# Main_MCU.net
KiCad netlist of a schematic drawn in Altium Designer
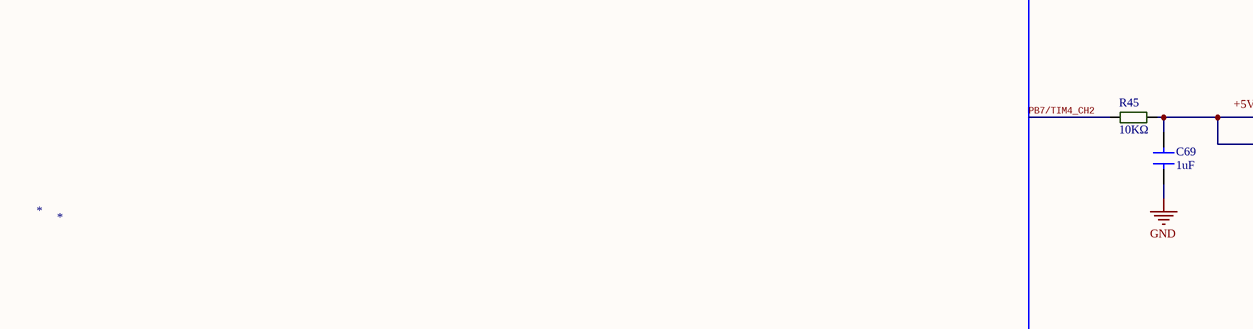
[diagram p0: Main MCU.SchDoc, left]
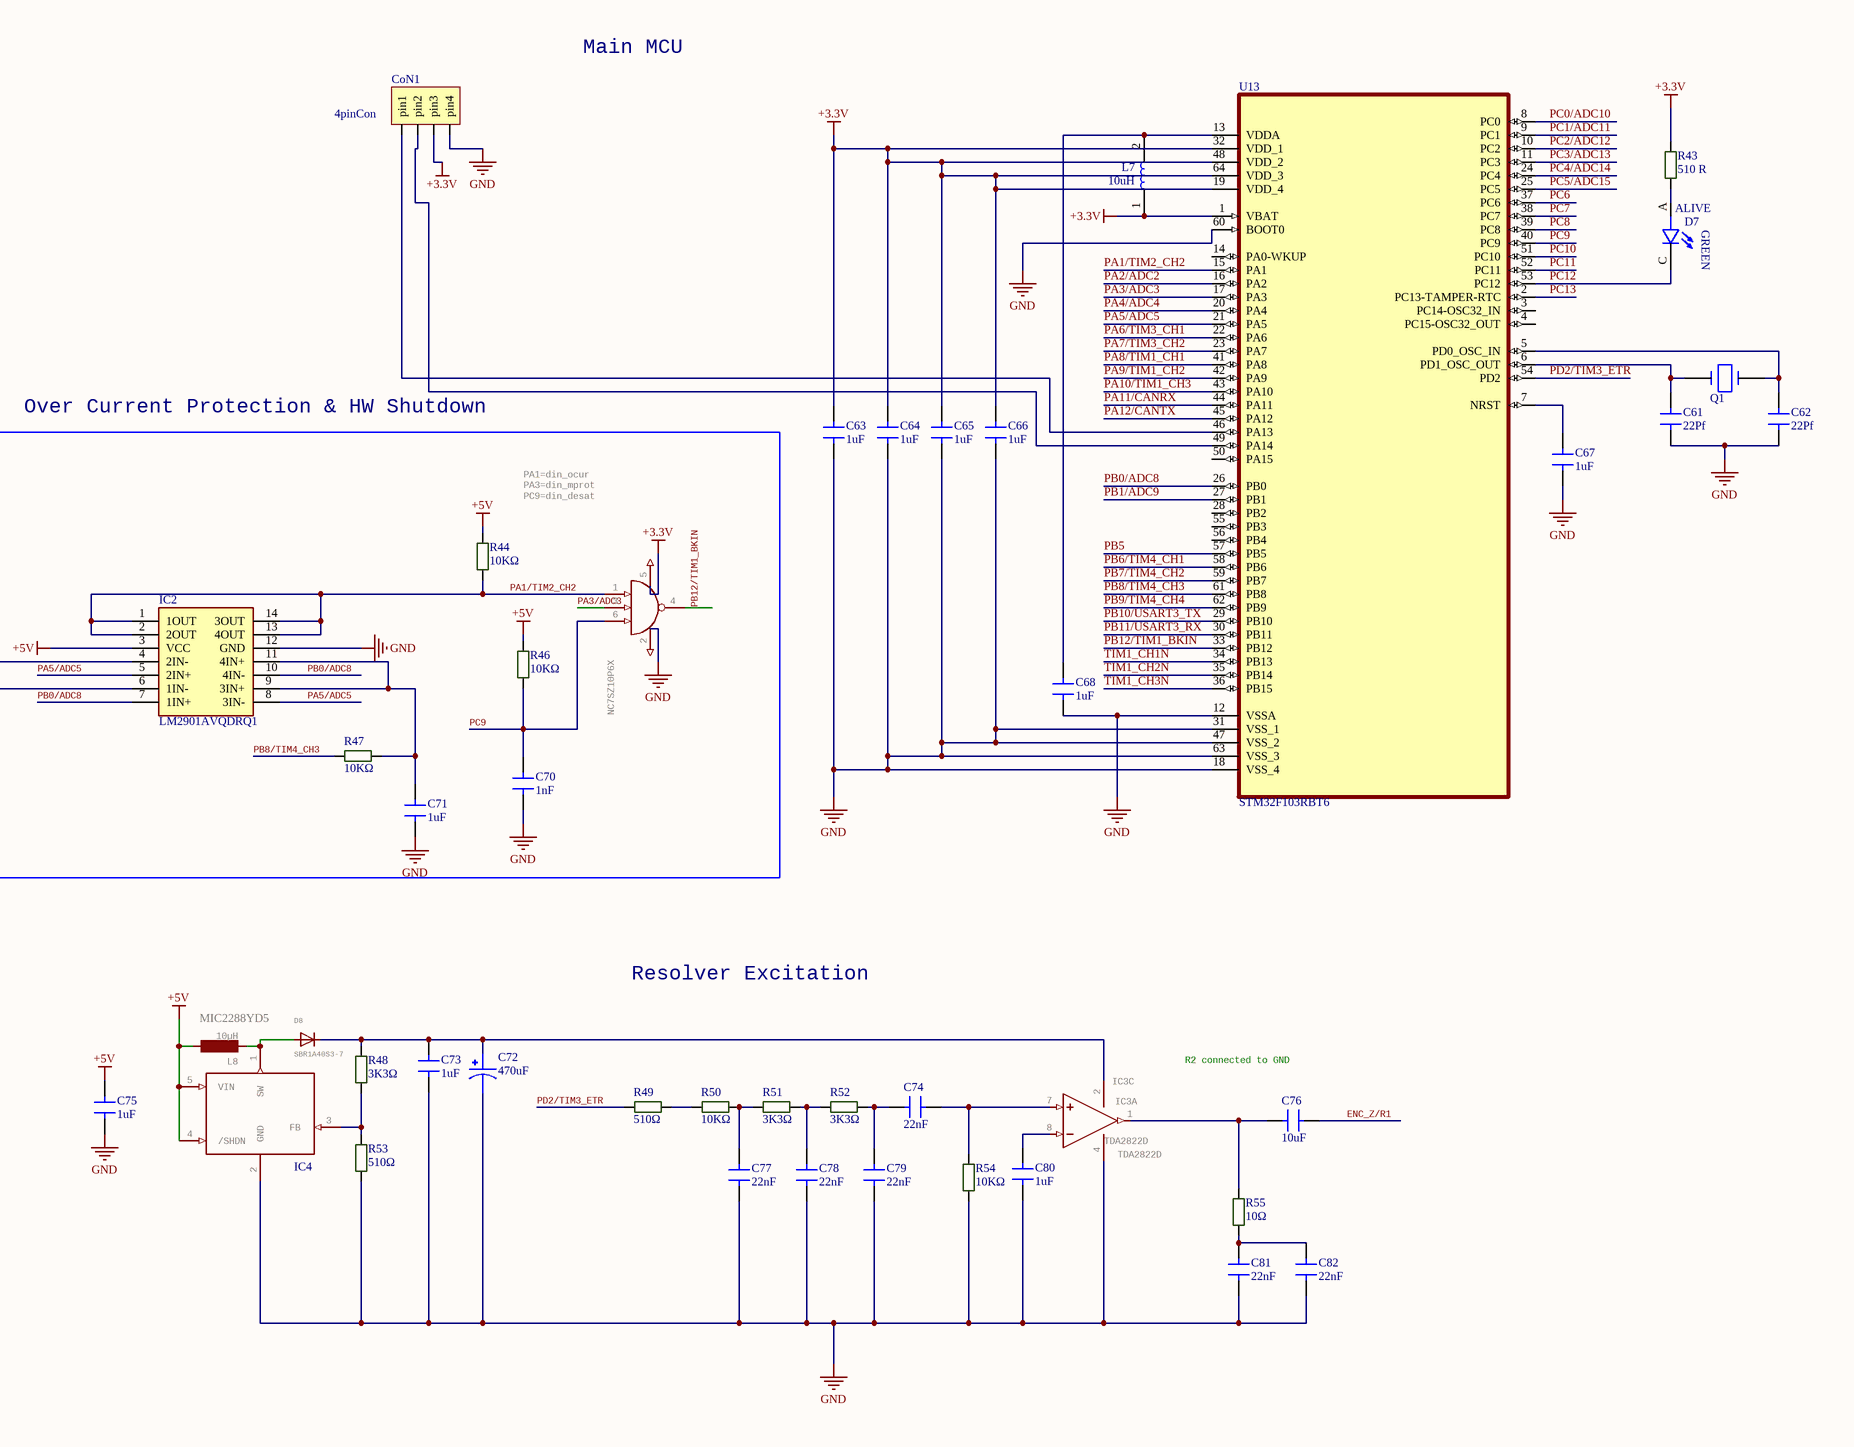
[diagram p1: Main MCU.SchDoc, right]

(export (version "E")
  (design (tool "Eeschema 10.0.6"))
  (components
    (comp (ref "C61")
      (value "22Pf")
      (footprint "C-0603W")
      (libsource (lib "Gate Driver Board") (part "C-0603"))
    )
    (comp (ref "C62")
      (value "22Pf")
      (footprint "C-0603W")
      (libsource (lib "Gate Driver Board") (part "C-0603"))
    )
    (comp (ref "C63")
      (value "1uF")
      (footprint "C-0603W")
      (libsource (lib "Gate Driver Board") (part "C-0603"))
    )
    (comp (ref "C64")
      (value "1uF")
      (footprint "C-0603W")
      (libsource (lib "Gate Driver Board") (part "C-0603"))
    )
    (comp (ref "C65")
      (value "1uF")
      (footprint "C-0603W")
      (libsource (lib "Gate Driver Board") (part "C-0603"))
    )
    (comp (ref "C66")
      (value "1uF")
      (footprint "C-0603W")
      (libsource (lib "Gate Driver Board") (part "C-0603"))
    )
    (comp (ref "C67")
      (value "1uF")
      (footprint "C-0603W")
      (libsource (lib "Gate Driver Board") (part "C-0603"))
    )
    (comp (ref "C68")
      (value "1uF")
      (footprint "C-0603W")
      (libsource (lib "Gate Driver Board") (part "C-0603"))
    )
    (comp (ref "C69")
      (value "1uF")
      (footprint "C-0603W")
      (libsource (lib "Gate Driver Board") (part "C-0603"))
    )
    (comp (ref "C70")
      (value "1nF")
      (footprint "C-0603W")
      (libsource (lib "Gate Driver Board") (part "C-0603"))
    )
    (comp (ref "C71")
      (value "1uF")
      (footprint "C-0603W")
      (libsource (lib "Gate Driver Board") (part "C-0603"))
    )
    (comp (ref "C72")
      (value "470uF")
      (footprint "CapSmdElc")
      (libsource (lib "PROJE") (part "100 uF Electr Cap"))
    )
    (comp (ref "C73")
      (value "1uF")
      (footprint "C-0603W")
      (libsource (lib "Gate Driver Board") (part "C-0603"))
    )
    (comp (ref "C74")
      (value "22nF")
      (footprint "C-0603W")
      (libsource (lib "Gate Driver Board") (part "C-0603"))
    )
    (comp (ref "C75")
      (value "1uF")
      (footprint "C-0603W")
      (libsource (lib "Gate Driver Board") (part "C-0603"))
    )
    (comp (ref "C76")
      (value "10uF")
      (footprint "C-0805")
      (libsource (lib "Gate Driver Board") (part "C-0805"))
    )
    (comp (ref "C77")
      (value "22nF")
      (footprint "C-0603W")
      (libsource (lib "Gate Driver Board") (part "C-0603"))
    )
    (comp (ref "C78")
      (value "22nF")
      (footprint "C-0603W")
      (libsource (lib "Gate Driver Board") (part "C-0603"))
    )
    (comp (ref "C79")
      (value "22nF")
      (footprint "C-0603W")
      (libsource (lib "Gate Driver Board") (part "C-0603"))
    )
    (comp (ref "C80")
      (value "1uF")
      (footprint "C-0603W")
      (libsource (lib "Gate Driver Board") (part "C-0603"))
    )
    (comp (ref "C81")
      (value "22nF")
      (footprint "C-0603W")
      (libsource (lib "Gate Driver Board") (part "C-0603"))
    )
    (comp (ref "C82")
      (value "22nF")
      (footprint "C-0603W")
      (libsource (lib "Gate Driver Board") (part "C-0603"))
    )
    (comp (ref "CoN1")
      (value "4pinCon")
      (footprint "4pinCon")
      (libsource (lib "Gate Driver Board") (part "4pinCon"))
    )
    (comp (ref "D7")
      (value "ALIVE")
      (footprint "LED_7012X1")
      (description "Green LED Indication - Discrete 1.7V 0805 (2012 Metric)")
      (fields (field (name "MP") "7012X1"))
      (libsource (lib "Gate Driver Board") (part "ALIVE"))
    )
    (comp (ref "D8")
      (value "*")
      (footprint "SOD-323F")
      (fields (field (name "ALTIUM_VALUE") "SBR1A40S3-7"))
      (libsource (lib "adafruit") (part "DIODESOD-323F"))
    )
    (comp (ref "IC1")
      (value "NC7SZ10P6X")
      (footprint "SC70-6")
      (description "3-input NAND gate")
      (libsource (lib "Gate Driver Board") (part "74*1G10X"))
    )
    (comp (ref "IC2")
      (value "LM2901AVQDRQ1")
      (footprint "SamacSys:SOIC127P600X175-14N")
      (description "Integrated Circuit")
      (fields (field (name "MOUSER PART NUMBER") "595-LM2901AVQDRQ1"))
      (libsource (lib "*") (part "LM2901AVQDRQ1"))
    )
    (comp (ref "IC3")
      (value "TDA2822D")
      (footprint "SO08")
      (description "OP AMP")
      (libsource (lib "Gate Driver Board") (part "TDA2822D"))
    )
    (comp (ref "IC4")
      (value "MIC2288YD5")
      (footprint "SOT23-5L")
      (libsource (lib "adafruit") (part "MIC2288YD5"))
    )
    (comp (ref "L7")
      (value "10uH")
      (footprint "INDC2012X87N")
      (description "FIXED IND 10UH 300MA 884 MOHM")
      (fields (field (name "MP") "MLZ2012M100HTD25"))
      (libsource (lib "Gate Driver Board") (part "MLZ2012M100HTD25"))
    )
    (comp (ref "L8")
      (value "*")
      (footprint "L2825P")
      (description "INDUCTOR, European symbol")
      (fields (field (name "ALTIUM_VALUE") "10µH"))
      (libsource (lib "rcl") (part "L-EUL2825P"))
    )
    (comp (ref "Q1")
      (value "Crystal 8MHz")
      (footprint "5032-2P")
      (description "32MHz Â±30ppm Crystal 18pF 40 Ohms HC-49/US")
      (fields (field (name "MF") "Abracon") (field (name "DIGI-KEY_PART_NUMBER") "535-9888-1-ND"))
      (libsource (lib "Gate Driver Board") (part "Crystal 8MHz"))
    )
    (comp (ref "R43")
      (value "510 R")
      (footprint "R-0603R")
      (libsource (lib "Gate Driver Board") (part "R-0603"))
    )
    (comp (ref "R44")
      (value "10KΩ")
      (footprint "R-0603R")
      (libsource (lib "Gate Driver Board") (part "R-0603"))
    )
    (comp (ref "R45")
      (value "10KΩ")
      (footprint "R-0603R")
      (libsource (lib "Gate Driver Board") (part "R-0603"))
    )
    (comp (ref "R46")
      (value "10KΩ")
      (footprint "R-0603R")
      (libsource (lib "Gate Driver Board") (part "R-0603"))
    )
    (comp (ref "R47")
      (value "10KΩ")
      (footprint "R-0603R")
      (libsource (lib "Gate Driver Board") (part "R-0603"))
    )
    (comp (ref "R48")
      (value "3K3Ω")
      (footprint "R-0603R")
      (libsource (lib "Gate Driver Board") (part "R-0603"))
    )
    (comp (ref "R49")
      (value "510Ω")
      (footprint "R-0603R")
      (libsource (lib "Gate Driver Board") (part "R-0603"))
    )
    (comp (ref "R50")
      (value "10KΩ")
      (footprint "R-0603R")
      (libsource (lib "Gate Driver Board") (part "R-0603"))
    )
    (comp (ref "R51")
      (value "3K3Ω")
      (footprint "R-0603R")
      (libsource (lib "Gate Driver Board") (part "R-0603"))
    )
    (comp (ref "R52")
      (value "3K3Ω")
      (footprint "R-0603R")
      (libsource (lib "Gate Driver Board") (part "R-0603"))
    )
    (comp (ref "R53")
      (value "510Ω")
      (footprint "R-0603R")
      (libsource (lib "Gate Driver Board") (part "R-0603"))
    )
    (comp (ref "R54")
      (value "10KΩ")
      (footprint "R-0603R")
      (libsource (lib "Gate Driver Board") (part "R-0603"))
    )
    (comp (ref "R55")
      (value "10Ω")
      (footprint "R-0603R")
      (libsource (lib "Gate Driver Board") (part "R-0603"))
    )
    (comp (ref "U13")
      (value "STM32F103RBT6")
      (footprint "QFP50P1200X1200X160-64N")
      (description "ARMÂ® CortexÂ®-M3 STM32F1 Microcontroller IC 32-Bit 72MHz 128KB _128K x 8_ FLASH")
      (fields (field (name "MF") "STMicroelectronics"))
      (libsource (lib "Gate Driver Board") (part "STM32F103RBT6"))
    )
  )
  (nets
    (net (code "1") (name "+3.3V") (class "Default")
      (node (ref "C63") (pin "2") (pinfunction "2_2") (pintype "passive"))
      (node (ref "C64") (pin "2") (pinfunction "2_2") (pintype "passive"))
      (node (ref "C65") (pin "2") (pinfunction "2_2") (pintype "passive"))
      (node (ref "C66") (pin "2") (pinfunction "2_2") (pintype "passive"))
      (node (ref "CoN1") (pin "3") (pinfunction "pin3_3") (pintype "passive"))
      (node (ref "IC1") (pin "5") (pinfunction "I0_5") (pintype "input"))
      (node (ref "L7") (pin "1") (pinfunction "1_1") (pintype "passive"))
      (node (ref "R43") (pin "2") (pinfunction "2_2") (pintype "passive"))
      (node (ref "U13") (pin "1") (pinfunction "VBAT_1") (pintype "input"))
      (node (ref "U13") (pin "19") (pinfunction "VDD_4_19") (pintype "power_in"))
      (node (ref "U13") (pin "32") (pinfunction "VDD_1_32") (pintype "power_in"))
      (node (ref "U13") (pin "48") (pinfunction "VDD_2_48") (pintype "power_in"))
      (node (ref "U13") (pin "64") (pinfunction "VDD_3_64") (pintype "power_in"))
    )
    (net (code "2") (name "+5V") (class "Default")
      (node (ref "C75") (pin "2") (pinfunction "2_2") (pintype "passive"))
      (node (ref "IC2") (pin "3") (pinfunction "VCC_3") (pintype "passive"))
      (node (ref "IC4") (pin "4") (pinfunction "/SHDN_4") (pintype "input"))
      (node (ref "IC4") (pin "5") (pinfunction "VIN_5") (pintype "input"))
      (node (ref "L8") (pin "1") (pinfunction "1_1") (pintype "passive"))
      (node (ref "R44") (pin "2") (pinfunction "2_2") (pintype "passive"))
      (node (ref "R46") (pin "2") (pinfunction "2_2") (pintype "passive"))
    )
    (net (code "3") (name "/ENC_Z{slash}R1") (class "Default")
      (node (ref "C76") (pin "2") (pinfunction "2_2") (pintype "passive"))
    )
    (net (code "4") (name "/PA1{slash}TIM2_CH2") (class "Default")
      (node (ref "IC1") (pin "1") (pinfunction "I0_1") (pintype "input"))
      (node (ref "IC2") (pin "1") (pinfunction "1OUT_1") (pintype "passive"))
      (node (ref "IC2") (pin "13") (pinfunction "4OUT_13") (pintype "passive"))
      (node (ref "IC2") (pin "14") (pinfunction "3OUT_14") (pintype "passive"))
      (node (ref "IC2") (pin "2") (pinfunction "2OUT_2") (pintype "passive"))
      (node (ref "R44") (pin "1") (pinfunction "1_1") (pintype "passive"))
      (node (ref "U13") (pin "15") (pinfunction "PA1_15") (pintype "bidirectional"))
    )
    (net (code "5") (name "/PA2{slash}ADC2") (class "Default")
      (node (ref "U13") (pin "16") (pinfunction "PA2_16") (pintype "bidirectional"))
    )
    (net (code "6") (name "/PA3{slash}ADC3") (class "Default")
      (node (ref "IC1") (pin "3") (pinfunction "I1_3") (pintype "input"))
      (node (ref "U13") (pin "17") (pinfunction "PA3_17") (pintype "bidirectional"))
    )
    (net (code "7") (name "/PA4{slash}ADC4") (class "Default")
      (node (ref "U13") (pin "20") (pinfunction "PA4_20") (pintype "bidirectional"))
    )
    (net (code "8") (name "/PA5{slash}ADC5") (class "Default")
      (node (ref "IC2") (pin "5") (pinfunction "2IN+_5") (pintype "passive"))
      (node (ref "IC2") (pin "8") (pinfunction "3IN-_8") (pintype "passive"))
      (node (ref "U13") (pin "21") (pinfunction "PA5_21") (pintype "bidirectional"))
    )
    (net (code "9") (name "/PA6{slash}TIM3_CH1") (class "Default")
      (node (ref "U13") (pin "22") (pinfunction "PA6_22") (pintype "bidirectional"))
    )
    (net (code "10") (name "/PA7{slash}TIM3_CH2") (class "Default")
      (node (ref "U13") (pin "23") (pinfunction "PA7_23") (pintype "bidirectional"))
    )
    (net (code "11") (name "/PA8{slash}TIM1_CH1") (class "Default")
      (node (ref "U13") (pin "41") (pinfunction "PA8_41") (pintype "bidirectional"))
    )
    (net (code "12") (name "/PA9{slash}TIM1_CH2") (class "Default")
      (node (ref "U13") (pin "42") (pinfunction "PA9_42") (pintype "bidirectional"))
    )
    (net (code "13") (name "/PA10{slash}TIM1_CH3") (class "Default")
      (node (ref "U13") (pin "43") (pinfunction "PA10_43") (pintype "bidirectional"))
    )
    (net (code "14") (name "/PA11{slash}CANRX") (class "Default")
      (node (ref "U13") (pin "44") (pinfunction "PA11_44") (pintype "bidirectional"))
    )
    (net (code "15") (name "/PA12{slash}CANTX") (class "Default")
      (node (ref "U13") (pin "45") (pinfunction "PA12_45") (pintype "bidirectional"))
    )
    (net (code "16") (name "/PB0{slash}ADC8") (class "Default")
      (node (ref "IC2") (pin "10") (pinfunction "4IN-_10") (pintype "passive"))
      (node (ref "IC2") (pin "7") (pinfunction "1IN+_7") (pintype "passive"))
      (node (ref "U13") (pin "26") (pinfunction "PB0_26") (pintype "bidirectional"))
    )
    (net (code "17") (name "/PB1{slash}ADC9") (class "Default")
      (node (ref "U13") (pin "27") (pinfunction "PB1_27") (pintype "bidirectional"))
    )
    (net (code "18") (name "/PB5") (class "Default")
      (node (ref "U13") (pin "57") (pinfunction "PB5_57") (pintype "bidirectional"))
    )
    (net (code "19") (name "/PB6{slash}TIM4_CH1") (class "Default")
      (node (ref "U13") (pin "58") (pinfunction "PB6_58") (pintype "bidirectional"))
    )
    (net (code "20") (name "/PB7{slash}TIM4_CH2") (class "Default")
      (node (ref "R45") (pin "1") (pinfunction "1_1") (pintype "passive"))
      (node (ref "U13") (pin "59") (pinfunction "PB7_59") (pintype "bidirectional"))
    )
    (net (code "21") (name "/PB8{slash}TIM4_CH3") (class "Default")
      (node (ref "R47") (pin "1") (pinfunction "1_1") (pintype "passive"))
      (node (ref "U13") (pin "61") (pinfunction "PB8_61") (pintype "bidirectional"))
    )
    (net (code "22") (name "/PB9{slash}TIM4_CH4") (class "Default")
      (node (ref "U13") (pin "62") (pinfunction "PB9_62") (pintype "bidirectional"))
    )
    (net (code "23") (name "/PB10{slash}USART3_TX") (class "Default")
      (node (ref "U13") (pin "29") (pinfunction "PB10_29") (pintype "bidirectional"))
    )
    (net (code "24") (name "/PB11{slash}USART3_RX") (class "Default")
      (node (ref "U13") (pin "30") (pinfunction "PB11_30") (pintype "bidirectional"))
    )
    (net (code "25") (name "/PB12{slash}TIM1_BKIN") (class "Default")
      (node (ref "IC1") (pin "4") (pinfunction "O_4") (pintype "open_collector"))
      (node (ref "U13") (pin "33") (pinfunction "PB12_33") (pintype "bidirectional"))
    )
    (net (code "26") (name "/PC0{slash}ADC10") (class "Default")
      (node (ref "U13") (pin "8") (pinfunction "PC0_8") (pintype "bidirectional"))
    )
    (net (code "27") (name "/PC1{slash}ADC11") (class "Default")
      (node (ref "U13") (pin "9") (pinfunction "PC1_9") (pintype "bidirectional"))
    )
    (net (code "28") (name "/PC2{slash}ADC12") (class "Default")
      (node (ref "U13") (pin "10") (pinfunction "PC2_10") (pintype "bidirectional"))
    )
    (net (code "29") (name "/PC3{slash}ADC13") (class "Default")
      (node (ref "U13") (pin "11") (pinfunction "PC3_11") (pintype "bidirectional"))
    )
    (net (code "30") (name "/PC4{slash}ADC14") (class "Default")
      (node (ref "U13") (pin "24") (pinfunction "PC4_24") (pintype "bidirectional"))
    )
    (net (code "31") (name "/PC5{slash}ADC15") (class "Default")
      (node (ref "U13") (pin "25") (pinfunction "PC5_25") (pintype "bidirectional"))
    )
    (net (code "32") (name "/PC6") (class "Default")
      (node (ref "U13") (pin "37") (pinfunction "PC6_37") (pintype "bidirectional"))
    )
    (net (code "33") (name "/PC7") (class "Default")
      (node (ref "U13") (pin "38") (pinfunction "PC7_38") (pintype "bidirectional"))
    )
    (net (code "34") (name "/PC8") (class "Default")
      (node (ref "U13") (pin "39") (pinfunction "PC8_39") (pintype "bidirectional"))
    )
    (net (code "35") (name "/PC9") (class "Default")
      (node (ref "C70") (pin "2") (pinfunction "2_2") (pintype "passive"))
      (node (ref "IC1") (pin "6") (pinfunction "I2_6") (pintype "input"))
      (node (ref "R46") (pin "1") (pinfunction "1_1") (pintype "passive"))
      (node (ref "U13") (pin "40") (pinfunction "PC9_40") (pintype "bidirectional"))
    )
    (net (code "36") (name "/PC10") (class "Default")
      (node (ref "U13") (pin "51") (pinfunction "PC10_51") (pintype "bidirectional"))
    )
    (net (code "37") (name "/PC11") (class "Default")
      (node (ref "U13") (pin "52") (pinfunction "PC11_52") (pintype "bidirectional"))
    )
    (net (code "38") (name "/PC12") (class "Default")
      (node (ref "D7") (pin "C") (pinfunction "C_C") (pintype "passive"))
      (node (ref "U13") (pin "53") (pinfunction "PC12_53") (pintype "bidirectional"))
    )
    (net (code "39") (name "/PC13") (class "Default")
      (node (ref "U13") (pin "2") (pinfunction "PC13-TAMPER-RTC_2") (pintype "bidirectional"))
    )
    (net (code "40") (name "/PD2{slash}TIM3_ETR") (class "Default")
      (node (ref "R49") (pin "2") (pinfunction "2_2") (pintype "passive"))
      (node (ref "U13") (pin "54") (pinfunction "PD2_54") (pintype "bidirectional"))
    )
    (net (code "41") (name "/TIM1_CH1N") (class "Default")
      (node (ref "U13") (pin "34") (pinfunction "PB13_34") (pintype "bidirectional"))
    )
    (net (code "42") (name "/TIM1_CH2N") (class "Default")
      (node (ref "U13") (pin "35") (pinfunction "PB14_35") (pintype "bidirectional"))
    )
    (net (code "43") (name "/TIM1_CH3N") (class "Default")
      (node (ref "U13") (pin "36") (pinfunction "PB15_36") (pintype "bidirectional"))
    )
    (net (code "44") (name "GND") (class "Default")
      (node (ref "C61") (pin "1") (pinfunction "1_1") (pintype "passive"))
      (node (ref "C62") (pin "1") (pinfunction "1_1") (pintype "passive"))
      (node (ref "C63") (pin "1") (pinfunction "1_1") (pintype "passive"))
      (node (ref "C64") (pin "1") (pinfunction "1_1") (pintype "passive"))
      (node (ref "C65") (pin "1") (pinfunction "1_1") (pintype "passive"))
      (node (ref "C66") (pin "1") (pinfunction "1_1") (pintype "passive"))
      (node (ref "C67") (pin "1") (pinfunction "1_1") (pintype "passive"))
      (node (ref "C68") (pin "1") (pinfunction "1_1") (pintype "passive"))
      (node (ref "C69") (pin "1") (pinfunction "1_1") (pintype "passive"))
      (node (ref "C70") (pin "1") (pinfunction "1_1") (pintype "passive"))
      (node (ref "C71") (pin "1") (pinfunction "1_1") (pintype "passive"))
      (node (ref "C72") (pin "2") (pinfunction "2_2") (pintype "passive"))
      (node (ref "C73") (pin "1") (pinfunction "1_1") (pintype "passive"))
      (node (ref "C75") (pin "1") (pinfunction "1_1") (pintype "passive"))
      (node (ref "C77") (pin "1") (pinfunction "1_1") (pintype "passive"))
      (node (ref "C78") (pin "1") (pinfunction "1_1") (pintype "passive"))
      (node (ref "C79") (pin "1") (pinfunction "1_1") (pintype "passive"))
      (node (ref "C80") (pin "1") (pinfunction "1_1") (pintype "passive"))
      (node (ref "C81") (pin "1") (pinfunction "1_1") (pintype "passive"))
      (node (ref "C82") (pin "1") (pinfunction "1_1") (pintype "passive"))
      (node (ref "CoN1") (pin "4") (pinfunction "pin4_4") (pintype "passive"))
      (node (ref "IC1") (pin "2") (pinfunction "I0_2") (pintype "input"))
      (node (ref "IC2") (pin "12") (pinfunction "GND_12") (pintype "passive"))
      (node (ref "IC3") (pin "4") (pinfunction "V-_4") (pintype "power_in"))
      (node (ref "IC4") (pin "2") (pinfunction "GND_2") (pintype "power_in"))
      (node (ref "R53") (pin "2") (pinfunction "2_2") (pintype "passive"))
      (node (ref "R54") (pin "1") (pinfunction "1_1") (pintype "passive"))
      (node (ref "U13") (pin "12") (pinfunction "VSSA_12") (pintype "passive"))
      (node (ref "U13") (pin "18") (pinfunction "VSS_4_18") (pintype "passive"))
      (node (ref "U13") (pin "31") (pinfunction "VSS_1_31") (pintype "passive"))
      (node (ref "U13") (pin "47") (pinfunction "VSS_2_47") (pintype "passive"))
      (node (ref "U13") (pin "60") (pinfunction "BOOT0_60") (pintype "input"))
      (node (ref "U13") (pin "63") (pinfunction "VSS_3_63") (pintype "passive"))
    )
    (net (code "45") (name "Net-(C74-Pad2)") (class "Default")
      (node (ref "C74") (pin "2") (pinfunction "2_2") (pintype "passive"))
      (node (ref "C79") (pin "2") (pinfunction "2_2") (pintype "passive"))
      (node (ref "R52") (pin "2") (pinfunction "2_2") (pintype "passive"))
    )
    (net (code "46") (name "Net-(C77-Pad2)") (class "Default")
      (node (ref "C77") (pin "2") (pinfunction "2_2") (pintype "passive"))
      (node (ref "R50") (pin "1") (pinfunction "1_1") (pintype "passive"))
      (node (ref "R51") (pin "1") (pinfunction "1_1") (pintype "passive"))
    )
    (net (code "47") (name "Net-(C78-Pad2)") (class "Default")
      (node (ref "C78") (pin "2") (pinfunction "2_2") (pintype "passive"))
      (node (ref "R51") (pin "2") (pinfunction "2_2") (pintype "passive"))
      (node (ref "R52") (pin "1") (pinfunction "1_1") (pintype "passive"))
    )
    (net (code "48") (name "Net-(C81-Pad2)") (class "Default")
      (node (ref "C81") (pin "2") (pinfunction "2_2") (pintype "passive"))
      (node (ref "C82") (pin "2") (pinfunction "2_2") (pintype "passive"))
      (node (ref "R55") (pin "2") (pinfunction "2_2") (pintype "passive"))
    )
    (net (code "49") (name "Net-(CoN1-pin1)") (class "Default")
      (node (ref "CoN1") (pin "1") (pinfunction "pin1_1") (pintype "passive"))
      (node (ref "U13") (pin "46") (pinfunction "PA13_46") (pintype "bidirectional"))
    )
    (net (code "50") (name "Net-(CoN1-pin2)") (class "Default")
      (node (ref "CoN1") (pin "2") (pinfunction "pin2_2") (pintype "passive"))
      (node (ref "U13") (pin "49") (pinfunction "PA14_49") (pintype "bidirectional"))
    )
    (net (code "51") (name "Net-(D7-PadA)") (class "Default")
      (node (ref "D7") (pin "A") (pinfunction "A_A") (pintype "passive"))
      (node (ref "R43") (pin "1") (pinfunction "1_1") (pintype "passive"))
    )
    (net (code "52") (name "Net-(IC2-1IN-)") (class "Default")
      (node (ref "C69") (pin "2") (pinfunction "2_2") (pintype "passive"))
      (node (ref "IC2") (pin "4") (pinfunction "2IN-_4") (pintype "passive"))
      (node (ref "IC2") (pin "6") (pinfunction "1IN-_6") (pintype "passive"))
      (node (ref "R45") (pin "2") (pinfunction "2_2") (pintype "passive"))
    )
    (net (code "53") (name "Net-(IC2-3IN+)") (class "Default")
      (node (ref "C71") (pin "2") (pinfunction "2_2") (pintype "passive"))
      (node (ref "IC2") (pin "11") (pinfunction "4IN+_11") (pintype "passive"))
      (node (ref "IC2") (pin "9") (pinfunction "3IN+_9") (pintype "passive"))
      (node (ref "R47") (pin "2") (pinfunction "2_2") (pintype "passive"))
    )
    (net (code "54") (name "Net-(IC3A-+IN)") (class "Default")
      (node (ref "C74") (pin "1") (pinfunction "1_1") (pintype "passive"))
      (node (ref "IC3") (pin "7") (pinfunction "+IN_7") (pintype "input"))
      (node (ref "R54") (pin "2") (pinfunction "2_2") (pintype "passive"))
    )
    (net (code "55") (name "Net-(IC3A--IN)") (class "Default")
      (node (ref "C80") (pin "2") (pinfunction "2_2") (pintype "passive"))
      (node (ref "IC3") (pin "8") (pinfunction "-IN_8") (pintype "input"))
    )
    (net (code "56") (name "Net-(IC3A-OUT)") (class "Default")
      (node (ref "C76") (pin "1") (pinfunction "1_1") (pintype "passive"))
      (node (ref "IC3") (pin "1") (pinfunction "OUT_1") (pintype "output"))
      (node (ref "R55") (pin "1") (pinfunction "1_1") (pintype "passive"))
    )
    (net (code "57") (name "Net-(IC3C-V+)") (class "Default")
      (node (ref "C72") (pin "1") (pinfunction "1_1") (pintype "passive"))
      (node (ref "C73") (pin "2") (pinfunction "2_2") (pintype "passive"))
      (node (ref "D8") (pin "C") (pinfunction "C_C") (pintype "passive"))
      (node (ref "IC3") (pin "2") (pinfunction "V+_2") (pintype "power_in"))
      (node (ref "R48") (pin "2") (pinfunction "2_2") (pintype "passive"))
    )
    (net (code "58") (name "Net-(IC4-FB)") (class "Default")
      (node (ref "IC4") (pin "3") (pinfunction "FB_3") (pintype "input"))
      (node (ref "R48") (pin "1") (pinfunction "1_1") (pintype "passive"))
      (node (ref "R53") (pin "1") (pinfunction "1_1") (pintype "passive"))
    )
    (net (code "59") (name "Net-(IC4-SW)") (class "Default")
      (node (ref "D8") (pin "A") (pinfunction "A_A") (pintype "passive"))
      (node (ref "IC4") (pin "1") (pinfunction "SW_1") (pintype "output"))
      (node (ref "L8") (pin "2") (pinfunction "2_2") (pintype "passive"))
    )
    (net (code "60") (name "Net-(R49-Pad1)") (class "Default")
      (node (ref "R49") (pin "1") (pinfunction "1_1") (pintype "passive"))
      (node (ref "R50") (pin "2") (pinfunction "2_2") (pintype "passive"))
    )
    (net (code "61") (name "Net-(U13-NRST)") (class "Default")
      (node (ref "C67") (pin "2") (pinfunction "2_2") (pintype "passive"))
      (node (ref "U13") (pin "7") (pinfunction "NRST_7") (pintype "bidirectional"))
    )
    (net (code "62") (name "Net-(U13-PD0_OSC_IN)") (class "Default")
      (node (ref "C62") (pin "2") (pinfunction "2_2") (pintype "passive"))
      (node (ref "Q1") (pin "2") (pinfunction "2_2") (pintype "passive"))
      (node (ref "U13") (pin "5") (pinfunction "PD0_OSC_IN_5") (pintype "bidirectional"))
    )
    (net (code "63") (name "Net-(U13-PD1_OSC_OUT)") (class "Default")
      (node (ref "C61") (pin "2") (pinfunction "2_2") (pintype "passive"))
      (node (ref "Q1") (pin "1") (pinfunction "1_1") (pintype "passive"))
      (node (ref "U13") (pin "6") (pinfunction "PD1_OSC_OUT_6") (pintype "bidirectional"))
    )
    (net (code "64") (name "Net-(U13-VDDA)") (class "Default")
      (node (ref "C68") (pin "2") (pinfunction "2_2") (pintype "passive"))
      (node (ref "L7") (pin "2") (pinfunction "2_2") (pintype "passive"))
      (node (ref "U13") (pin "13") (pinfunction "VDDA_13") (pintype "power_in"))
    )
    (net (code "65") (name "unconnected-(U13-PA0-WKUP-Pad14)") (class "Default")
      (node (ref "U13") (pin "14") (pinfunction "PA0-WKUP_14") (pintype "bidirectional"))
    )
    (net (code "66") (name "unconnected-(U13-PA15-Pad50)") (class "Default")
      (node (ref "U13") (pin "50") (pinfunction "PA15_50") (pintype "bidirectional"))
    )
    (net (code "67") (name "unconnected-(U13-PB2-Pad28)") (class "Default")
      (node (ref "U13") (pin "28") (pinfunction "PB2_28") (pintype "bidirectional"))
    )
    (net (code "68") (name "unconnected-(U13-PB3-Pad55)") (class "Default")
      (node (ref "U13") (pin "55") (pinfunction "PB3_55") (pintype "bidirectional"))
    )
    (net (code "69") (name "unconnected-(U13-PB4-Pad56)") (class "Default")
      (node (ref "U13") (pin "56") (pinfunction "PB4_56") (pintype "bidirectional"))
    )
    (net (code "70") (name "unconnected-(U13-PC14-OSC32_IN-Pad3)") (class "Default")
      (node (ref "U13") (pin "3") (pinfunction "PC14-OSC32_IN_3") (pintype "bidirectional"))
    )
    (net (code "71") (name "unconnected-(U13-PC15-OSC32_OUT-Pad4)") (class "Default")
      (node (ref "U13") (pin "4") (pinfunction "PC15-OSC32_OUT_4") (pintype "bidirectional"))
    )
  )
)
